# U_I_Meter_Bottom.net
KiCad netlist of a schematic drawn in Altium Designer
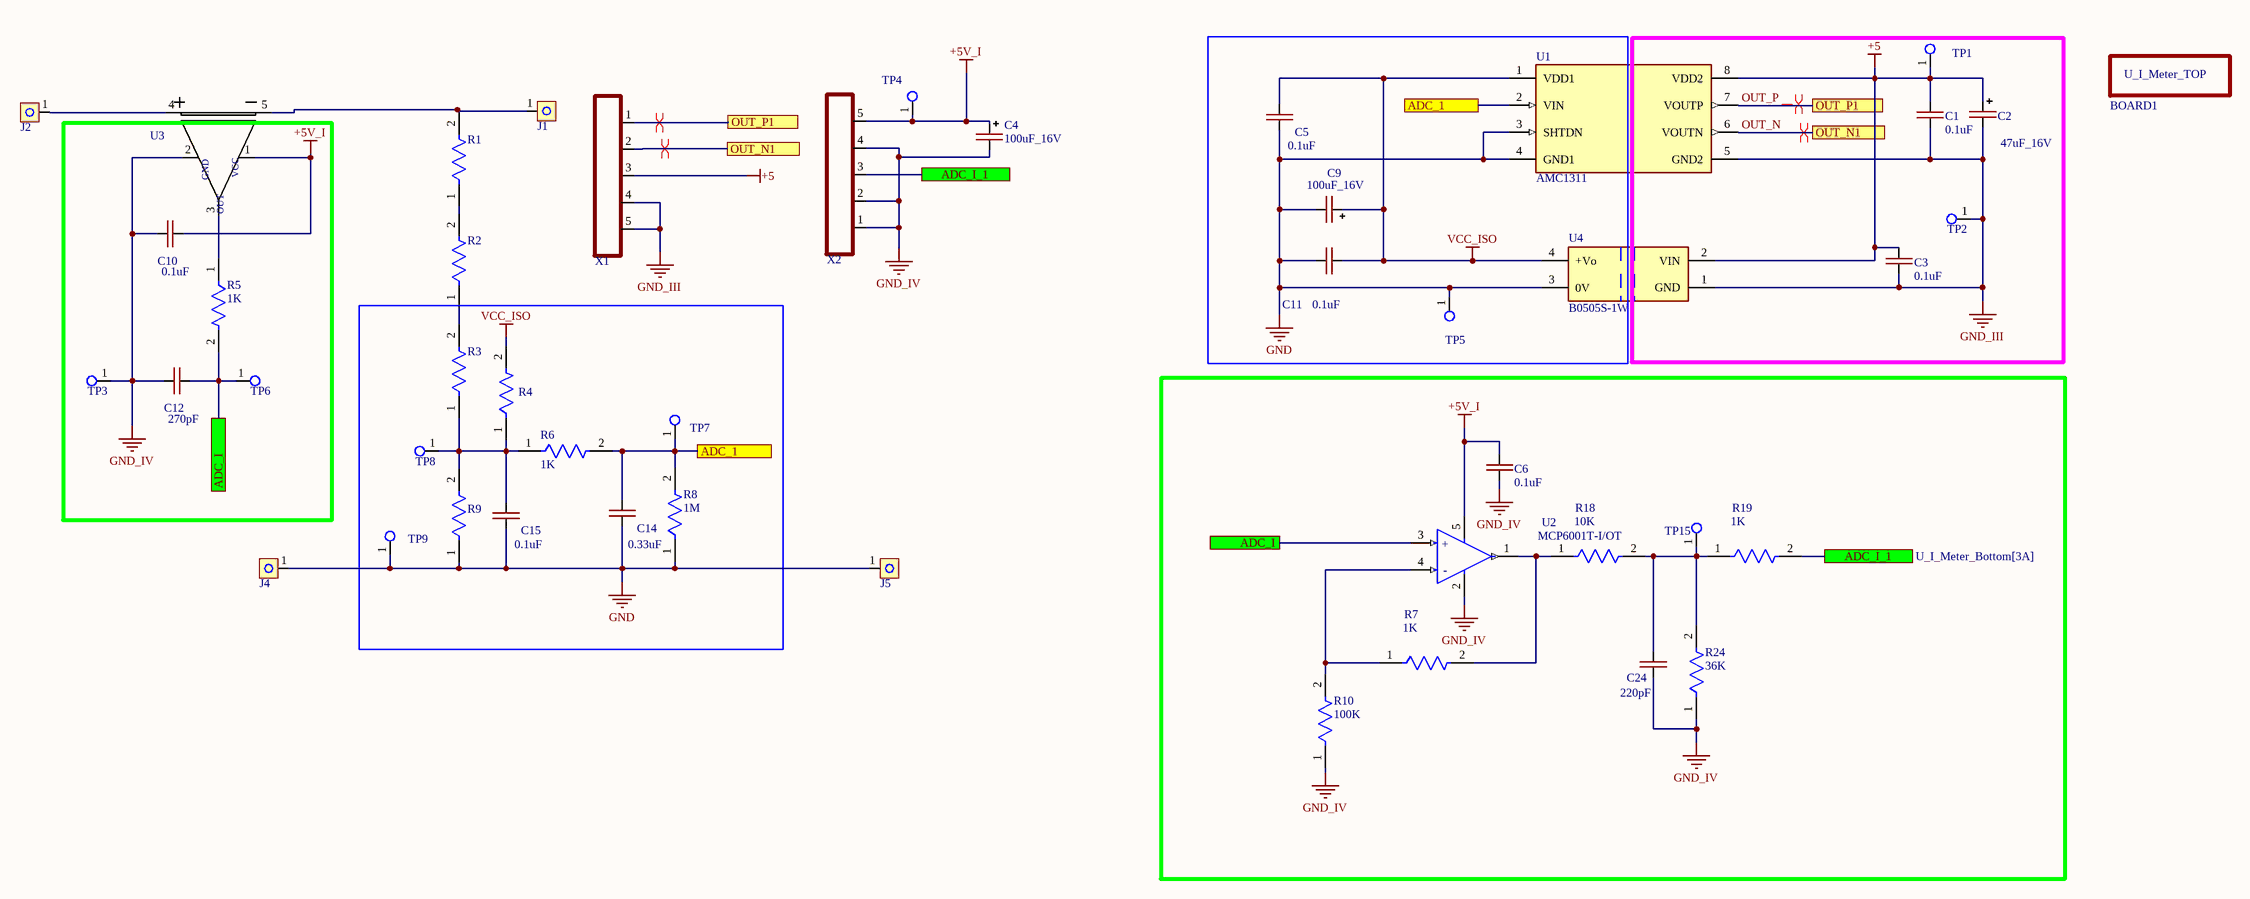
[diagram p0: U_I_Meter_Bottom.SchDoc]

(export (version "E")
  (design (tool "Eeschema 10.0.6"))
  (components
    (comp (ref "BOARD1")
      (value "U_I_Meter_TOP")
      (footprint "U_I_Meter_TOP")
      (libsource (lib "U_I_Meter_TOP") (part "U_I_Meter_TOP"))
    )
    (comp (ref "C1")
      (value "0.1uF")
      (footprint "CAP-0805")
      (libsource (lib "PASSIVE_COMPONENTS") (part "CAP-NON-POLAR"))
    )
    (comp (ref "C2")
      (value "47uF_16V")
      (footprint "CAP-TAN-D")
      (libsource (lib "PASSIVE_COMPONENTS") (part "CAP-POLAR"))
    )
    (comp (ref "C3")
      (value "0.1uF")
      (footprint "CAP-0805")
      (libsource (lib "PASSIVE_COMPONENTS") (part "CAP-NON-POLAR"))
    )
    (comp (ref "C4")
      (value "100uF_16V")
      (footprint "CAP-TAN-D")
      (libsource (lib "PASSIVE_COMPONENTS") (part "CAP_POL_SMD"))
    )
    (comp (ref "C5")
      (value "0.1uF")
      (footprint "CAP-0805")
      (libsource (lib "PASSIVE_COMPONENTS") (part "CAP-NON-POLAR"))
    )
    (comp (ref "C6")
      (value "0.1uF")
      (footprint "CAP-0805")
      (libsource (lib "PASSIVE_COMPONENTS") (part "CAP-NON-POLAR"))
    )
    (comp (ref "C9")
      (value "100uF_16V")
      (footprint "CAP-TAN-D")
      (libsource (lib "PASSIVE_COMPONENTS") (part "CAP_POL_SMD"))
    )
    (comp (ref "C10")
      (value "0.1uF")
      (footprint "CAP-0805")
      (libsource (lib "PASSIVE_COMPONENTS") (part "CAP-NON-POLAR"))
    )
    (comp (ref "C11")
      (value "0.1uF")
      (footprint "CAP-0805")
      (libsource (lib "PASSIVE_COMPONENTS") (part "CAP-NON-POLAR"))
    )
    (comp (ref "C12")
      (value "270pF")
      (footprint "CAP-0805")
      (libsource (lib "PASSIVE_COMPONENTS") (part "CAP-NON-POLAR"))
    )
    (comp (ref "C14")
      (value "0.33uF")
      (footprint "CAP-0805")
      (libsource (lib "PASSIVE_COMPONENTS") (part "CAP-NON-POLAR"))
    )
    (comp (ref "C15")
      (value "0.1uF")
      (footprint "CAP-0805")
      (libsource (lib "PASSIVE_COMPONENTS") (part "CAP-NON-POLAR"))
    )
    (comp (ref "C24")
      (value "220pF")
      (footprint "CAP-0805")
      (libsource (lib "PASSIVE_COMPONENTS") (part "CAP-NON-POLAR"))
    )
    (comp (ref "J1")
      (value "MG_136_HT")
      (footprint "Conn_MEIGAN_MG136HT")
      (libsource (lib "") (part "Connector_MEIGAN_MG136HT_1"))
    )
    (comp (ref "J2")
      (value "MG_136_HT")
      (footprint "Conn_MEIGAN_MG136HT")
      (libsource (lib "Connectors") (part "Connector_MEIGAN_MG136HT"))
    )
    (comp (ref "J4")
      (value "MG_136_HT")
      (footprint "Conn_MEIGAN_MG136HT")
      (libsource (lib "Connectors") (part "Connector_MEIGAN_MG136HT"))
    )
    (comp (ref "J5")
      (value "MG_136_HT")
      (footprint "Conn_MEIGAN_MG136HT")
      (libsource (lib "") (part "Connector_MEIGAN_MG136HT_1"))
    )
    (comp (ref "R1")
      (value "~")
      (footprint "RES-2512")
      (libsource (lib "PASSIVE_COMPONENTS") (part "RES-CONST"))
    )
    (comp (ref "R2")
      (value "~")
      (footprint "RES-2512")
      (libsource (lib "PASSIVE_COMPONENTS") (part "RES-CONST"))
    )
    (comp (ref "R3")
      (value "~")
      (footprint "RES-2512")
      (libsource (lib "PASSIVE_COMPONENTS") (part "RES-CONST"))
    )
    (comp (ref "R4")
      (value "~")
      (footprint "RES-0805")
      (libsource (lib "PASSIVE_COMPONENTS") (part "RES-CONST"))
    )
    (comp (ref "R5")
      (value "1K")
      (footprint "RES-0805")
      (libsource (lib "PASSIVE_COMPONENTS") (part "RES-CONST"))
    )
    (comp (ref "R6")
      (value "1K")
      (footprint "RES-0805")
      (libsource (lib "PASSIVE_COMPONENTS") (part "RES-CONST"))
    )
    (comp (ref "R7")
      (value "1K")
      (footprint "RES-0805")
      (description "10K")
      (libsource (lib "PASSIVE_COMPONENTS") (part "RES-CONST"))
    )
    (comp (ref "R8")
      (value "1M")
      (footprint "RES-0805")
      (libsource (lib "PASSIVE_COMPONENTS") (part "RES-CONST"))
    )
    (comp (ref "R9")
      (value "RES_1210")
      (footprint "RES_SMD_1210_IPC_B")
      (libsource (lib "PASSIVE_COMPONENTS") (part "RES_1210"))
    )
    (comp (ref "R10")
      (value "100K")
      (footprint "RES-0805")
      (libsource (lib "PASSIVE_COMPONENTS") (part "RES-CONST"))
    )
    (comp (ref "R18")
      (value "10K")
      (footprint "RES-0805")
      (libsource (lib "PASSIVE_COMPONENTS") (part "RES-CONST"))
    )
    (comp (ref "R19")
      (value "1K")
      (footprint "RES-0805")
      (description "10K")
      (libsource (lib "PASSIVE_COMPONENTS") (part "RES-CONST"))
    )
    (comp (ref "R24")
      (value "36K")
      (footprint "RES-0805")
      (libsource (lib "PASSIVE_COMPONENTS") (part "RES-CONST"))
    )
    (comp (ref "TP1")
      (value "Test_Point_PCB")
      (footprint "Test_Point")
      (description "Test_Point")
      (libsource (lib "Connectors") (part "TP_PCB?"))
    )
    (comp (ref "TP2")
      (value "Test_Point_PCB")
      (footprint "Test_Point")
      (description "Test_Point")
      (libsource (lib "Connectors") (part "TP_PCB?"))
    )
    (comp (ref "TP3")
      (value "Test_Point_PCB")
      (footprint "Test_Point")
      (description "Test_Point")
      (libsource (lib "Connectors") (part "TP_PCB?"))
    )
    (comp (ref "TP4")
      (value "Test_Point_PCB")
      (footprint "Test_Point")
      (description "Test_Point")
      (libsource (lib "Connectors") (part "TP_PCB?"))
    )
    (comp (ref "TP5")
      (value "Test_Point_PCB")
      (footprint "Pin_Test_Point(Pink)")
      (description "Test_Point")
      (libsource (lib "Connectors") (part "TP_PCB?"))
    )
    (comp (ref "TP6")
      (value "Test_Point_PCB")
      (footprint "Test_Point")
      (description "Test_Point")
      (libsource (lib "Connectors") (part "TP_PCB?"))
    )
    (comp (ref "TP7")
      (value "Test_Point_PCB")
      (footprint "Test_Point")
      (description "Test_Point")
      (libsource (lib "Connectors") (part "TP_PCB?"))
    )
    (comp (ref "TP8")
      (value "Test_Point_PCB")
      (footprint "Test_Point")
      (description "Test_Point")
      (libsource (lib "Connectors") (part "TP_PCB?"))
    )
    (comp (ref "TP9")
      (value "Test_Point_PCB")
      (footprint "Test_Point")
      (description "Test_Point")
      (libsource (lib "Connectors") (part "TP_PCB?"))
    )
    (comp (ref "TP15")
      (value "Test_Point_PCB")
      (footprint "Test_Point")
      (description "Test_Point")
      (libsource (lib "Connectors") (part "TP_PCB?"))
    )
    (comp (ref "U1")
      (value "AMC1311")
      (footprint "FP-DWV0008A-MFG")
      (libsource (lib "Integrated_Circuts") (part "AMC1311"))
    )
    (comp (ref "U2")
      (value "MCP6001T-I/OT")
      (footprint "SOT-23-5")
      (description "IC OPAMP GP 1 CIRCUIT SOT23-5")
      (fields (field (name "VOLTAGE") "6V"))
      (libsource (lib "Integrated_Circuts") (part "MCP6001T"))
    )
    (comp (ref "U3")
      (value "ACS758")
      (footprint "ACS758-100")
      (libsource (lib "Integrated_Circuts") (part "ACS758"))
    )
    (comp (ref "U4")
      (value "B0505S-1W")
      (footprint "B0505S-1W")
      (libsource (lib "Integrated_Circuts") (part "B0505S-1W"))
    )
    (comp (ref "X1")
      (value "CONN-5-PIN")
      (footprint "CONN-PLS-5-2.54mm")
      (libsource (lib "PLS-5__") (part "CONN-5-PIN"))
    )
    (comp (ref "X2")
      (value "CONN-5-PIN")
      (footprint "CONN-PLS-5-2.54mm")
      (libsource (lib "") (part "CONN-5-PIN_1"))
    )
  )
  (nets
    (net (code "1") (name "+5") (class "Default")
      (node (ref "C1") (pin "1") (pinfunction "1_1") (pintype "passive"))
      (node (ref "C2") (pin "1") (pinfunction "+_1") (pintype "passive"))
      (node (ref "C3") (pin "1") (pinfunction "1_1") (pintype "passive"))
      (node (ref "TP1") (pin "1") (pinfunction "G9_1") (pintype "passive"))
      (node (ref "U1") (pin "8") (pinfunction "VDD2_8") (pintype "power_in"))
      (node (ref "U4") (pin "2") (pinfunction "VIN_2") (pintype "power_in"))
      (node (ref "X1") (pin "3") (pinfunction "3_3") (pintype "passive"))
    )
    (net (code "2") (name "+5V_I") (class "Default")
      (node (ref "C10") (pin "2") (pinfunction "2_2") (pintype "passive"))
      (node (ref "C4") (pin "1") (pinfunction "+_1") (pintype "passive"))
      (node (ref "C6") (pin "2") (pinfunction "2_2") (pintype "passive"))
      (node (ref "TP4") (pin "1") (pinfunction "G9_1") (pintype "passive"))
      (node (ref "U2") (pin "5") (pinfunction "VDD_5") (pintype "power_in"))
      (node (ref "U3") (pin "1") (pinfunction "+VCC_1") (pintype "passive"))
      (node (ref "X2") (pin "5") (pinfunction "5_5") (pintype "passive"))
    )
    (net (code "3") (name "/ADC_1") (class "Default")
      (node (ref "C14") (pin "2") (pinfunction "2_2") (pintype "passive"))
      (node (ref "R6") (pin "2") (pinfunction "2_2") (pintype "passive"))
      (node (ref "R8") (pin "2") (pinfunction "2_2") (pintype "passive"))
      (node (ref "TP7") (pin "1") (pinfunction "G9_1") (pintype "passive"))
      (node (ref "U1") (pin "2") (pinfunction "VIN_2") (pintype "input"))
    )
    (net (code "4") (name "/ADC_I") (class "Default")
      (node (ref "C12") (pin "2") (pinfunction "2_2") (pintype "passive"))
      (node (ref "R5") (pin "2") (pinfunction "2_2") (pintype "passive"))
      (node (ref "TP6") (pin "1") (pinfunction "G9_1") (pintype "passive"))
      (node (ref "U2") (pin "3") (pinfunction "VIN+_3") (pintype "input"))
    )
    (net (code "5") (name "/ADC_I_1") (class "Default")
      (node (ref "R19") (pin "2") (pinfunction "2_2") (pintype "passive"))
      (node (ref "X2") (pin "3") (pinfunction "3_3") (pintype "passive"))
    )
    (net (code "6") (name "/OUT_N") (class "Default")
      (node (ref "U1") (pin "6") (pinfunction "VOUTN_6") (pintype "output"))
      (node (ref "X1") (pin "2") (pinfunction "2_2") (pintype "passive"))
    )
    (net (code "7") (name "/OUT_P") (class "Default")
      (node (ref "U1") (pin "7") (pinfunction "VOUTP_7") (pintype "output"))
      (node (ref "X1") (pin "1") (pinfunction "1_1") (pintype "passive"))
    )
    (net (code "8") (name "GND") (class "Default")
      (node (ref "C11") (pin "2") (pinfunction "2_2") (pintype "passive"))
      (node (ref "C14") (pin "1") (pinfunction "1_1") (pintype "passive"))
      (node (ref "C15") (pin "1") (pinfunction "1_1") (pintype "passive"))
      (node (ref "C5") (pin "1") (pinfunction "1_1") (pintype "passive"))
      (node (ref "C9") (pin "2") (pinfunction "-_2") (pintype "passive"))
      (node (ref "J4") (pin "1") (pinfunction "17_1") (pintype "passive"))
      (node (ref "J5") (pin "1") (pinfunction "17_1") (pintype "passive"))
      (node (ref "R8") (pin "1") (pinfunction "1_1") (pintype "passive"))
      (node (ref "R9") (pin "1") (pinfunction "1_1") (pintype "passive"))
      (node (ref "TP5") (pin "1") (pinfunction "G9_1") (pintype "passive"))
      (node (ref "TP9") (pin "1") (pinfunction "G9_1") (pintype "passive"))
      (node (ref "U1") (pin "3") (pinfunction "SHTDN_3") (pintype "input"))
      (node (ref "U1") (pin "4") (pinfunction "GND1_4") (pintype "power_in"))
      (node (ref "U4") (pin "3") (pinfunction "0V_3") (pintype "power_in"))
    )
    (net (code "9") (name "GND_III") (class "Default")
      (node (ref "C1") (pin "2") (pinfunction "2_2") (pintype "passive"))
      (node (ref "C2") (pin "2") (pinfunction "-_2") (pintype "passive"))
      (node (ref "C3") (pin "2") (pinfunction "2_2") (pintype "passive"))
      (node (ref "TP2") (pin "1") (pinfunction "G9_1") (pintype "passive"))
      (node (ref "U1") (pin "5") (pinfunction "GND2_5") (pintype "power_in"))
      (node (ref "U4") (pin "1") (pinfunction "GND_1") (pintype "power_in"))
      (node (ref "X1") (pin "4") (pinfunction "4_4") (pintype "passive"))
      (node (ref "X1") (pin "5") (pinfunction "5_5") (pintype "passive"))
    )
    (net (code "10") (name "GND_IV") (class "Default")
      (node (ref "C10") (pin "1") (pinfunction "1_1") (pintype "passive"))
      (node (ref "C12") (pin "1") (pinfunction "1_1") (pintype "passive"))
      (node (ref "C24") (pin "1") (pinfunction "1_1") (pintype "passive"))
      (node (ref "C4") (pin "2") (pinfunction "-_2") (pintype "passive"))
      (node (ref "C6") (pin "1") (pinfunction "1_1") (pintype "passive"))
      (node (ref "R10") (pin "1") (pinfunction "1_1") (pintype "passive"))
      (node (ref "R24") (pin "1") (pinfunction "1_1") (pintype "passive"))
      (node (ref "TP3") (pin "1") (pinfunction "G9_1") (pintype "passive"))
      (node (ref "U2") (pin "2") (pinfunction "VSS_2") (pintype "power_in"))
      (node (ref "U3") (pin "2") (pinfunction "GND_2") (pintype "passive"))
      (node (ref "X2") (pin "1") (pinfunction "1_1") (pintype "passive"))
      (node (ref "X2") (pin "2") (pinfunction "2_2") (pintype "passive"))
      (node (ref "X2") (pin "4") (pinfunction "4_4") (pintype "passive"))
    )
    (net (code "11") (name "Net-(J1-17)") (class "Default")
      (node (ref "J1") (pin "1") (pinfunction "17_1") (pintype "passive"))
      (node (ref "R1") (pin "2") (pinfunction "2_2") (pintype "passive"))
      (node (ref "U3") (pin "5") (pinfunction "-IP_5") (pintype "passive"))
    )
    (net (code "12") (name "Net-(J2-17)") (class "Default")
      (node (ref "J2") (pin "1") (pinfunction "17_1") (pintype "passive"))
      (node (ref "U3") (pin "4") (pinfunction "+IP_4") (pintype "passive"))
    )
    (net (code "13") (name "Net-(R1-Pad1)") (class "Default")
      (node (ref "R1") (pin "1") (pinfunction "1_1") (pintype "passive"))
      (node (ref "R2") (pin "2") (pinfunction "2_2") (pintype "passive"))
    )
    (net (code "14") (name "Net-(R2-Pad1)") (class "Default")
      (node (ref "R2") (pin "1") (pinfunction "1_1") (pintype "passive"))
      (node (ref "R3") (pin "2") (pinfunction "2_2") (pintype "passive"))
    )
    (net (code "15") (name "Net-(TP8-G9)") (class "Default")
      (node (ref "C15") (pin "2") (pinfunction "2_2") (pintype "passive"))
      (node (ref "R3") (pin "1") (pinfunction "1_1") (pintype "passive"))
      (node (ref "R4") (pin "1") (pinfunction "1_1") (pintype "passive"))
      (node (ref "R6") (pin "1") (pinfunction "1_1") (pintype "passive"))
      (node (ref "R9") (pin "2") (pinfunction "2_2") (pintype "passive"))
      (node (ref "TP8") (pin "1") (pinfunction "G9_1") (pintype "passive"))
    )
    (net (code "16") (name "Net-(TP15-G9)") (class "Default")
      (node (ref "C24") (pin "2") (pinfunction "2_2") (pintype "passive"))
      (node (ref "R18") (pin "2") (pinfunction "2_2") (pintype "passive"))
      (node (ref "R19") (pin "1") (pinfunction "1_1") (pintype "passive"))
      (node (ref "R24") (pin "2") (pinfunction "2_2") (pintype "passive"))
      (node (ref "TP15") (pin "1") (pinfunction "G9_1") (pintype "passive"))
    )
    (net (code "17") (name "Net-(U2-VIN-)") (class "Default")
      (node (ref "R10") (pin "2") (pinfunction "2_2") (pintype "passive"))
      (node (ref "R7") (pin "1") (pinfunction "1_1") (pintype "passive"))
      (node (ref "U2") (pin "4") (pinfunction "VIN-_4") (pintype "input"))
    )
    (net (code "18") (name "Net-(U2-VOUT)") (class "Default")
      (node (ref "R18") (pin "1") (pinfunction "1_1") (pintype "passive"))
      (node (ref "R7") (pin "2") (pinfunction "2_2") (pintype "passive"))
      (node (ref "U2") (pin "1") (pinfunction "VOUT_1") (pintype "output"))
    )
    (net (code "19") (name "Net-(U3-OUT)") (class "Default")
      (node (ref "R5") (pin "1") (pinfunction "1_1") (pintype "passive"))
      (node (ref "U3") (pin "3") (pinfunction "OUT_3") (pintype "passive"))
    )
    (net (code "20") (name "VCC_ISO") (class "Default")
      (node (ref "C11") (pin "1") (pinfunction "1_1") (pintype "passive"))
      (node (ref "C5") (pin "2") (pinfunction "2_2") (pintype "passive"))
      (node (ref "C9") (pin "1") (pinfunction "+_1") (pintype "passive"))
      (node (ref "R4") (pin "2") (pinfunction "2_2") (pintype "passive"))
      (node (ref "U1") (pin "1") (pinfunction "VDD1_1") (pintype "power_in"))
      (node (ref "U4") (pin "4") (pinfunction "+Vo_4") (pintype "power_in"))
    )
  )
)
